# SCH-Button_LED_EasyEDA.net
KiCad netlist of a schematic drawn in EasyEDA
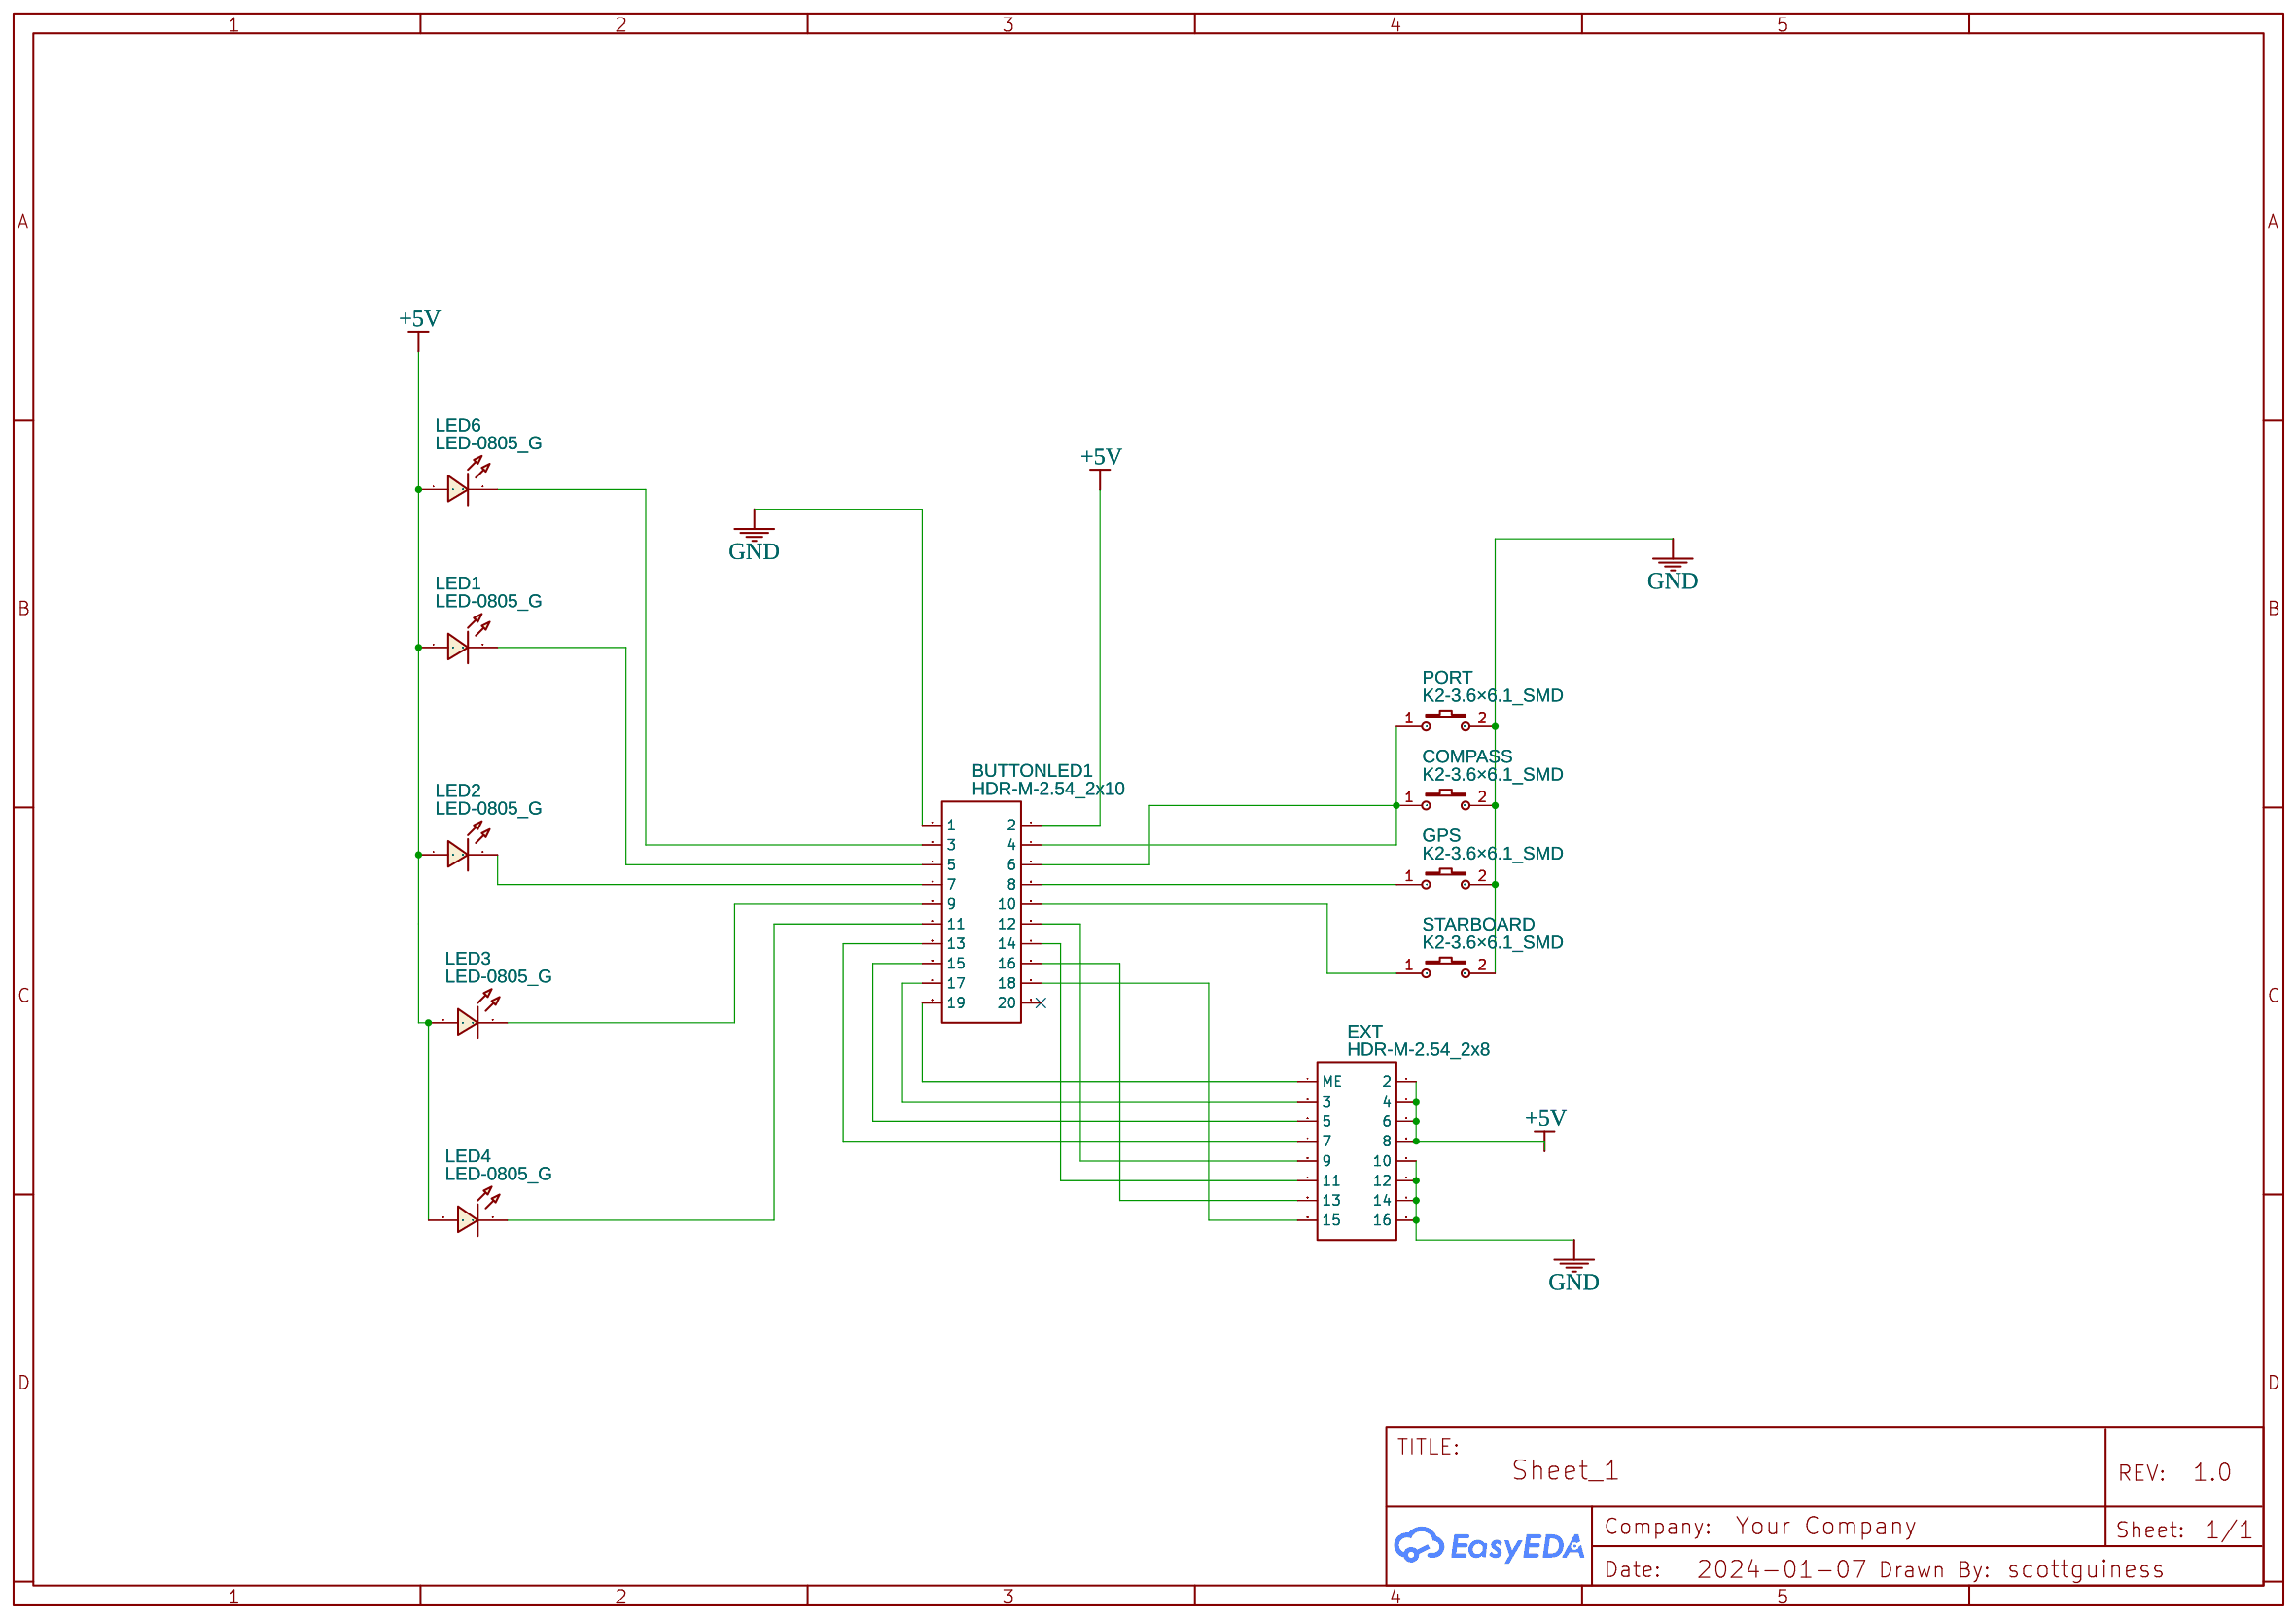
[diagram p0: schematic sheet]

(export (version "E")
  (design (tool "Eeschema 10.0.6"))
  (components
    (comp (ref "BUTTONLED1") (value "HDR-M-2.54_2x10") (libsource (lib "") (part "HDR-M-2.54_2x10")))
    (comp (ref "COMPASS")
      (value "K2-3.6×6.1_SMD")
      (fields (field (name "Manufacturer Part") "K2-1107ST-A4SW-06"))
      (libsource (lib "") (part "K2-3.6×6.1_SMD_3"))
    )
    (comp (ref "EXT") (value "HDR-M-2.54_2x8") (libsource (lib "") (part "HDR-M-2.54_2x8")))
    (comp (ref "GPS")
      (value "K2-3.6×6.1_SMD")
      (fields (field (name "Manufacturer Part") "K2-1107ST-A4SW-06"))
      (libsource (lib "") (part "K2-3.6×6.1_SMD_1"))
    )
    (comp (ref "LED1")
      (value "LED-0805_G")
      (fields (field (name "Manufacturer Part") "NCD0805G1") (field (name "Manufacturer") "国星光电"))
      (libsource (lib "") (part "LED-0805_G"))
    )
    (comp (ref "LED2")
      (value "LED-0805_G")
      (fields (field (name "Manufacturer Part") "NCD0805G1") (field (name "Manufacturer") "国星光电"))
      (libsource (lib "") (part "LED-0805_G"))
    )
    (comp (ref "LED3")
      (value "LED-0805_G")
      (fields (field (name "Manufacturer Part") "NCD0805G1") (field (name "Manufacturer") "国星光电"))
      (libsource (lib "") (part "LED-0805_G"))
    )
    (comp (ref "LED4")
      (value "LED-0805_G")
      (fields (field (name "Manufacturer Part") "NCD0805G1") (field (name "Manufacturer") "国星光电"))
      (libsource (lib "") (part "LED-0805_G"))
    )
    (comp (ref "LED6")
      (value "LED-0805_G")
      (fields (field (name "Manufacturer Part") "NCD0805G1") (field (name "Manufacturer") "国星光电"))
      (libsource (lib "") (part "LED-0805_G"))
    )
    (comp (ref "PORT")
      (value "K2-3.6×6.1_SMD")
      (fields (field (name "Manufacturer Part") "K2-1107ST-A4SW-06"))
      (libsource (lib "") (part "K2-3.6×6.1_SMD"))
    )
    (comp (ref "STARBOARD")
      (value "K2-3.6×6.1_SMD")
      (fields (field (name "Manufacturer Part") "K2-1107ST-A4SW-06"))
      (libsource (lib "") (part "K2-3.6×6.1_SMD_2"))
    )
  )
  (nets
    (net (code "1") (name "+5V") (class "Default")
      (node (ref "BUTTONLED1") (pin "2") (pinfunction "2_2") (pintype "unspecified"))
      (node (ref "EXT") (pin "2") (pinfunction "2_2") (pintype "input"))
      (node (ref "EXT") (pin "4") (pinfunction "4_4") (pintype "input"))
      (node (ref "EXT") (pin "6") (pinfunction "6_6") (pintype "input"))
      (node (ref "EXT") (pin "8") (pinfunction "8_8") (pintype "input"))
      (node (ref "LED1") (pin "1") (pinfunction "1_1") (pintype "unspecified"))
      (node (ref "LED2") (pin "1") (pinfunction "1_1") (pintype "unspecified"))
      (node (ref "LED3") (pin "1") (pinfunction "1_1") (pintype "unspecified"))
      (node (ref "LED4") (pin "1") (pinfunction "1_1") (pintype "unspecified"))
      (node (ref "LED6") (pin "1") (pinfunction "1_1") (pintype "unspecified"))
    )
    (net (code "2") (name "GND") (class "Default")
      (node (ref "BUTTONLED1") (pin "1") (pinfunction "1_1") (pintype "unspecified"))
      (node (ref "COMPASS") (pin "2") (pinfunction "2_2") (pintype "unspecified"))
      (node (ref "EXT") (pin "10") (pinfunction "10_10") (pintype "input"))
      (node (ref "EXT") (pin "12") (pinfunction "12_12") (pintype "input"))
      (node (ref "EXT") (pin "14") (pinfunction "14_14") (pintype "input"))
      (node (ref "EXT") (pin "16") (pinfunction "16_16") (pintype "input"))
      (node (ref "GPS") (pin "2") (pinfunction "2_2") (pintype "unspecified"))
      (node (ref "PORT") (pin "2") (pinfunction "2_2") (pintype "unspecified"))
      (node (ref "STARBOARD") (pin "2") (pinfunction "2_2") (pintype "unspecified"))
    )
    (net (code "3") (name "Net-(BUTTONLED1-Pad3)") (class "Default")
      (node (ref "BUTTONLED1") (pin "3") (pinfunction "3_3") (pintype "unspecified"))
      (node (ref "LED6") (pin "2") (pinfunction "2_2") (pintype "unspecified"))
    )
    (net (code "4") (name "Net-(BUTTONLED1-Pad4)") (class "Default")
      (node (ref "BUTTONLED1") (pin "4") (pinfunction "4_4") (pintype "unspecified"))
      (node (ref "BUTTONLED1") (pin "6") (pinfunction "6_6") (pintype "unspecified"))
      (node (ref "COMPASS") (pin "1") (pinfunction "1_1") (pintype "unspecified"))
      (node (ref "PORT") (pin "1") (pinfunction "1_1") (pintype "unspecified"))
    )
    (net (code "5") (name "Net-(BUTTONLED1-Pad5)") (class "Default")
      (node (ref "BUTTONLED1") (pin "5") (pinfunction "5_5") (pintype "unspecified"))
      (node (ref "LED1") (pin "2") (pinfunction "2_2") (pintype "unspecified"))
    )
    (net (code "6") (name "Net-(BUTTONLED1-Pad7)") (class "Default")
      (node (ref "BUTTONLED1") (pin "7") (pinfunction "7_7") (pintype "unspecified"))
      (node (ref "LED2") (pin "2") (pinfunction "2_2") (pintype "unspecified"))
    )
    (net (code "7") (name "Net-(BUTTONLED1-Pad8)") (class "Default")
      (node (ref "BUTTONLED1") (pin "8") (pinfunction "8_8") (pintype "unspecified"))
      (node (ref "GPS") (pin "1") (pinfunction "1_1") (pintype "unspecified"))
    )
    (net (code "8") (name "Net-(BUTTONLED1-Pad9)") (class "Default")
      (node (ref "BUTTONLED1") (pin "9") (pinfunction "9_9") (pintype "unspecified"))
      (node (ref "LED3") (pin "2") (pinfunction "2_2") (pintype "unspecified"))
    )
    (net (code "9") (name "Net-(BUTTONLED1-Pad10)") (class "Default")
      (node (ref "BUTTONLED1") (pin "10") (pinfunction "10_10") (pintype "unspecified"))
      (node (ref "STARBOARD") (pin "1") (pinfunction "1_1") (pintype "unspecified"))
    )
    (net (code "10") (name "Net-(BUTTONLED1-Pad11)") (class "Default")
      (node (ref "BUTTONLED1") (pin "11") (pinfunction "11_11") (pintype "unspecified"))
      (node (ref "LED4") (pin "2") (pinfunction "2_2") (pintype "unspecified"))
    )
    (net (code "11") (name "Net-(BUTTONLED1-Pad12)") (class "Default")
      (node (ref "BUTTONLED1") (pin "12") (pinfunction "12_12") (pintype "unspecified"))
      (node (ref "EXT") (pin "9") (pinfunction "9_9") (pintype "input"))
    )
    (net (code "12") (name "Net-(BUTTONLED1-Pad13)") (class "Default")
      (node (ref "BUTTONLED1") (pin "13") (pinfunction "13_13") (pintype "unspecified"))
      (node (ref "EXT") (pin "7") (pinfunction "7_7") (pintype "input"))
    )
    (net (code "13") (name "Net-(BUTTONLED1-Pad14)") (class "Default")
      (node (ref "BUTTONLED1") (pin "14") (pinfunction "14_14") (pintype "unspecified"))
      (node (ref "EXT") (pin "11") (pinfunction "11_11") (pintype "input"))
    )
    (net (code "14") (name "Net-(BUTTONLED1-Pad15)") (class "Default")
      (node (ref "BUTTONLED1") (pin "15") (pinfunction "15_15") (pintype "unspecified"))
      (node (ref "EXT") (pin "5") (pinfunction "5_5") (pintype "input"))
    )
    (net (code "15") (name "Net-(BUTTONLED1-Pad16)") (class "Default")
      (node (ref "BUTTONLED1") (pin "16") (pinfunction "16_16") (pintype "unspecified"))
      (node (ref "EXT") (pin "13") (pinfunction "13_13") (pintype "input"))
    )
    (net (code "16") (name "Net-(BUTTONLED1-Pad17)") (class "Default")
      (node (ref "BUTTONLED1") (pin "17") (pinfunction "17_17") (pintype "unspecified"))
      (node (ref "EXT") (pin "3") (pinfunction "3_3") (pintype "input"))
    )
    (net (code "17") (name "Net-(BUTTONLED1-Pad18)") (class "Default")
      (node (ref "BUTTONLED1") (pin "18") (pinfunction "18_18") (pintype "unspecified"))
      (node (ref "EXT") (pin "15") (pinfunction "15_15") (pintype "input"))
    )
    (net (code "18") (name "Net-(EXT-ME)") (class "Default")
      (node (ref "BUTTONLED1") (pin "19") (pinfunction "19_19") (pintype "unspecified"))
      (node (ref "EXT") (pin "1") (pinfunction "ME_1") (pintype "input"))
    )
    (net (code "19") (name "unconnected-(BUTTONLED1-Pad20)") (class "Default")
      (node (ref "BUTTONLED1") (pin "20") (pinfunction "20_20") (pintype "unspecified+no_connect"))
    )
  )
)
